# remote.net
KiCad netlist of a schematic drawn in EAGLE
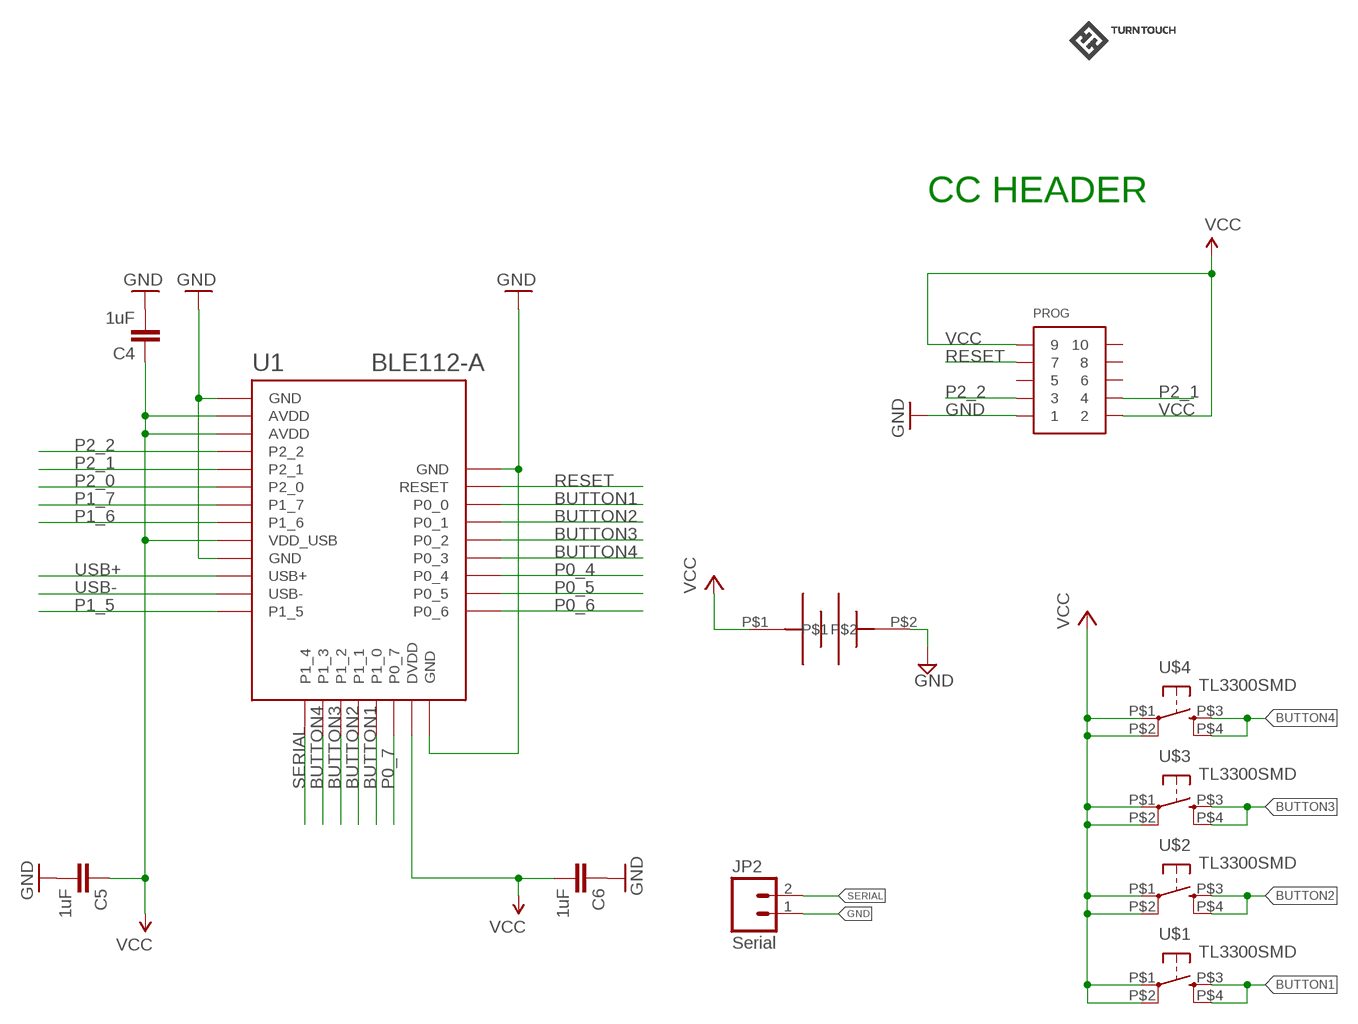
[diagram p0: schematic, sheet 1]

(export (version "E")
  (design (tool "Eeschema 10.0.6"))
  (components
    (comp (ref "C4")
      (value "1uF")
      (footprint "eagle-import:0603-CAP")
      (libsource (lib "eagle-import") (part "CAP0603-CAP"))
    )
    (comp (ref "C5")
      (value "1uF")
      (footprint "eagle-import:0603-CAP")
      (libsource (lib "eagle-import") (part "CAP0603-CAP"))
    )
    (comp (ref "C6")
      (value "1uF")
      (footprint "eagle-import:0603-CAP")
      (libsource (lib "eagle-import") (part "CAP0603-CAP"))
    )
    (comp (ref "JP2")
      (value "Serial")
      (footprint "eagle-import:1X02")
      (libsource (lib "eagle-import") (part "M02PTH"))
    )
    (comp (ref "LOGO")
      (value "TURNTOUCHLOGO200DPI")
      (footprint "eagle-import:LOGO")
      (libsource (lib "eagle-import") (part "TURNTOUCHLOGO200DPI"))
    )
    (comp (ref "PROG")
      (value "CONN_5-2-FTSH-V")
      (footprint "eagle-import:FTSH-105-DV")
      (libsource (lib "eagle-import") (part "CONN_5-2-FTSH-V"))
    )
    (comp (ref "U$1")
      (value "TL3300SMD")
      (footprint "eagle-import:TL3300")
      (libsource (lib "eagle-import") (part "TL3300SMD"))
    )
    (comp (ref "U$2")
      (value "TL3300SMD")
      (footprint "eagle-import:TL3300")
      (libsource (lib "eagle-import") (part "TL3300SMD"))
    )
    (comp (ref "U$3")
      (value "TL3300SMD")
      (footprint "eagle-import:TL3300")
      (libsource (lib "eagle-import") (part "TL3300SMD"))
    )
    (comp (ref "U$4")
      (value "TL3300SMD")
      (footprint "eagle-import:TL3300")
      (libsource (lib "eagle-import") (part "TL3300SMD"))
    )
    (comp (ref "U$6")
      (value "COINCELLHOLDER")
      (footprint "eagle-import:20MMCOINCELL")
      (libsource (lib "eagle-import") (part "COINCELLHOLDER"))
    )
    (comp (ref "U1")
      (value "BLE112-A")
      (footprint "eagle-import:BLE112-A")
      (libsource (lib "eagle-import") (part "BLE112-A-VISUAL"))
    )
  )
  (nets
    (net (code "1") (name "/P0_4") (class "Default")
      (node (ref "U1") (pin "P0_4") (pinfunction "P0_4_P0_4") (pintype "bidirectional"))
    )
    (net (code "2") (name "/P0_5") (class "Default")
      (node (ref "U1") (pin "P0_5") (pinfunction "P0_5_P0_5") (pintype "bidirectional"))
    )
    (net (code "3") (name "/P0_6") (class "Default")
      (node (ref "U1") (pin "P0_6") (pinfunction "P0_6_P0_6") (pintype "bidirectional"))
    )
    (net (code "4") (name "/P0_7") (class "Default")
      (node (ref "U1") (pin "P0_7") (pinfunction "P0_7_P0_7") (pintype "bidirectional"))
    )
    (net (code "5") (name "/P1_5") (class "Default")
      (node (ref "U1") (pin "P1_5") (pinfunction "P1_5_P1_5") (pintype "bidirectional"))
    )
    (net (code "6") (name "/P1_6") (class "Default")
      (node (ref "U1") (pin "P1_6") (pinfunction "P1_6_P1_6") (pintype "bidirectional"))
    )
    (net (code "7") (name "/P1_7") (class "Default")
      (node (ref "U1") (pin "P1_7") (pinfunction "P1_7_P1_7") (pintype "bidirectional"))
    )
    (net (code "8") (name "/P2_0") (class "Default")
      (node (ref "U1") (pin "P2_0") (pinfunction "P2_0_P2_0") (pintype "bidirectional"))
    )
    (net (code "9") (name "/P2_1") (class "Default")
      (node (ref "PROG") (pin "4") (pinfunction "4_4") (pintype "bidirectional"))
      (node (ref "U1") (pin "P2_1") (pinfunction "P2_1_P2_1") (pintype "bidirectional"))
    )
    (net (code "10") (name "/P2_2") (class "Default")
      (node (ref "PROG") (pin "3") (pinfunction "3_3") (pintype "bidirectional"))
      (node (ref "U1") (pin "P2_2") (pinfunction "P2_2_P2_2") (pintype "bidirectional"))
    )
    (net (code "11") (name "/RESET") (class "Default")
      (node (ref "PROG") (pin "7") (pinfunction "7_7") (pintype "bidirectional"))
      (node (ref "U1") (pin "RESET") (pinfunction "RESET_RESET") (pintype "input"))
    )
    (net (code "12") (name "/USB+") (class "Default")
      (node (ref "U1") (pin "USB+") (pinfunction "USB+_USB+") (pintype "bidirectional"))
    )
    (net (code "13") (name "/USB-") (class "Default")
      (node (ref "U1") (pin "USB-") (pinfunction "USB-_USB-") (pintype "bidirectional"))
    )
    (net (code "14") (name "BUTTON1") (class "Default")
      (node (ref "U$1") (pin "P$3") (pinfunction "S_P$3") (pintype "passive"))
      (node (ref "U$1") (pin "P$4") (pinfunction "S1_P$4") (pintype "passive"))
      (node (ref "U1") (pin "P0_0") (pinfunction "P0_0_P0_0") (pintype "bidirectional"))
      (node (ref "U1") (pin "P1_0") (pinfunction "P1_0_P1_0") (pintype "bidirectional"))
    )
    (net (code "15") (name "BUTTON2") (class "Default")
      (node (ref "U$2") (pin "P$3") (pinfunction "S_P$3") (pintype "passive"))
      (node (ref "U$2") (pin "P$4") (pinfunction "S1_P$4") (pintype "passive"))
      (node (ref "U1") (pin "P0_1") (pinfunction "P0_1_P0_1") (pintype "bidirectional"))
      (node (ref "U1") (pin "P1_1") (pinfunction "P1_1_P1_1") (pintype "bidirectional"))
    )
    (net (code "16") (name "BUTTON3") (class "Default")
      (node (ref "U$3") (pin "P$3") (pinfunction "S_P$3") (pintype "passive"))
      (node (ref "U$3") (pin "P$4") (pinfunction "S1_P$4") (pintype "passive"))
      (node (ref "U1") (pin "P0_2") (pinfunction "P0_2_P0_2") (pintype "bidirectional"))
      (node (ref "U1") (pin "P1_2") (pinfunction "P1_2_P1_2") (pintype "bidirectional"))
    )
    (net (code "17") (name "BUTTON4") (class "Default")
      (node (ref "U$4") (pin "P$3") (pinfunction "S_P$3") (pintype "passive"))
      (node (ref "U$4") (pin "P$4") (pinfunction "S1_P$4") (pintype "passive"))
      (node (ref "U1") (pin "P0_3") (pinfunction "P0_3_P0_3") (pintype "bidirectional"))
      (node (ref "U1") (pin "P1_3") (pinfunction "P1_3_P1_3") (pintype "bidirectional"))
    )
    (net (code "18") (name "GND") (class "Default")
      (node (ref "C4") (pin "2") (pinfunction "2_2") (pintype "passive"))
      (node (ref "C5") (pin "2") (pinfunction "2_2") (pintype "passive"))
      (node (ref "C6") (pin "1") (pinfunction "1_1") (pintype "passive"))
      (node (ref "JP2") (pin "1") (pinfunction "1_1") (pintype "passive"))
      (node (ref "PROG") (pin "1") (pinfunction "1_1") (pintype "bidirectional"))
      (node (ref "U$6") (pin "P$2") (pinfunction "P$2_P$2") (pintype "bidirectional"))
      (node (ref "U1") (pin "GND1") (pinfunction "GND_GND1") (pintype "power_in"))
      (node (ref "U1") (pin "GND2") (pinfunction "GND_GND2") (pintype "power_in"))
      (node (ref "U1") (pin "GND3") (pinfunction "GND_GND3") (pintype "power_in"))
      (node (ref "U1") (pin "GND4") (pinfunction "GND_GND4") (pintype "power_in"))
    )
    (net (code "19") (name "SERIAL") (class "Default")
      (node (ref "JP2") (pin "2") (pinfunction "2_2") (pintype "passive"))
      (node (ref "U1") (pin "P1_4") (pinfunction "P1_4_P1_4") (pintype "bidirectional"))
    )
    (net (code "20") (name "VCC") (class "Default")
      (node (ref "C4") (pin "1") (pinfunction "1_1") (pintype "passive"))
      (node (ref "C5") (pin "1") (pinfunction "1_1") (pintype "passive"))
      (node (ref "C6") (pin "2") (pinfunction "2_2") (pintype "passive"))
      (node (ref "PROG") (pin "2") (pinfunction "2_2") (pintype "bidirectional"))
      (node (ref "PROG") (pin "9") (pinfunction "9_9") (pintype "bidirectional"))
      (node (ref "U$1") (pin "P$1") (pinfunction "P_P$1") (pintype "passive"))
      (node (ref "U$1") (pin "P$2") (pinfunction "P1_P$2") (pintype "passive"))
      (node (ref "U$2") (pin "P$1") (pinfunction "P_P$1") (pintype "passive"))
      (node (ref "U$2") (pin "P$2") (pinfunction "P1_P$2") (pintype "passive"))
      (node (ref "U$3") (pin "P$1") (pinfunction "P_P$1") (pintype "passive"))
      (node (ref "U$3") (pin "P$2") (pinfunction "P1_P$2") (pintype "passive"))
      (node (ref "U$4") (pin "P$1") (pinfunction "P_P$1") (pintype "passive"))
      (node (ref "U$4") (pin "P$2") (pinfunction "P1_P$2") (pintype "passive"))
      (node (ref "U$6") (pin "P$1") (pinfunction "P$1_P$1") (pintype "bidirectional"))
      (node (ref "U1") (pin "AVDD1") (pinfunction "AVDD_AVDD1") (pintype "power_in"))
      (node (ref "U1") (pin "AVDD2") (pinfunction "AVDD_AVDD2") (pintype "power_in"))
      (node (ref "U1") (pin "DVDD") (pinfunction "DVDD_DVDD") (pintype "power_in"))
      (node (ref "U1") (pin "VDD_USB") (pinfunction "VDD_USB_VDD_USB") (pintype "power_in"))
    )
    (net (code "21") (name "unconnected-(PROG-Pad5)") (class "Default")
      (node (ref "PROG") (pin "5") (pinfunction "5_5") (pintype "bidirectional"))
    )
    (net (code "22") (name "unconnected-(PROG-Pad6)") (class "Default")
      (node (ref "PROG") (pin "6") (pinfunction "6_6") (pintype "bidirectional"))
    )
    (net (code "23") (name "unconnected-(PROG-Pad8)") (class "Default")
      (node (ref "PROG") (pin "8") (pinfunction "8_8") (pintype "bidirectional"))
    )
    (net (code "24") (name "unconnected-(PROG-Pad10)") (class "Default")
      (node (ref "PROG") (pin "10") (pinfunction "10_10") (pintype "bidirectional"))
    )
  )
)
